# UserInteractive.net
KiCad netlist of a schematic drawn in Altium Designer
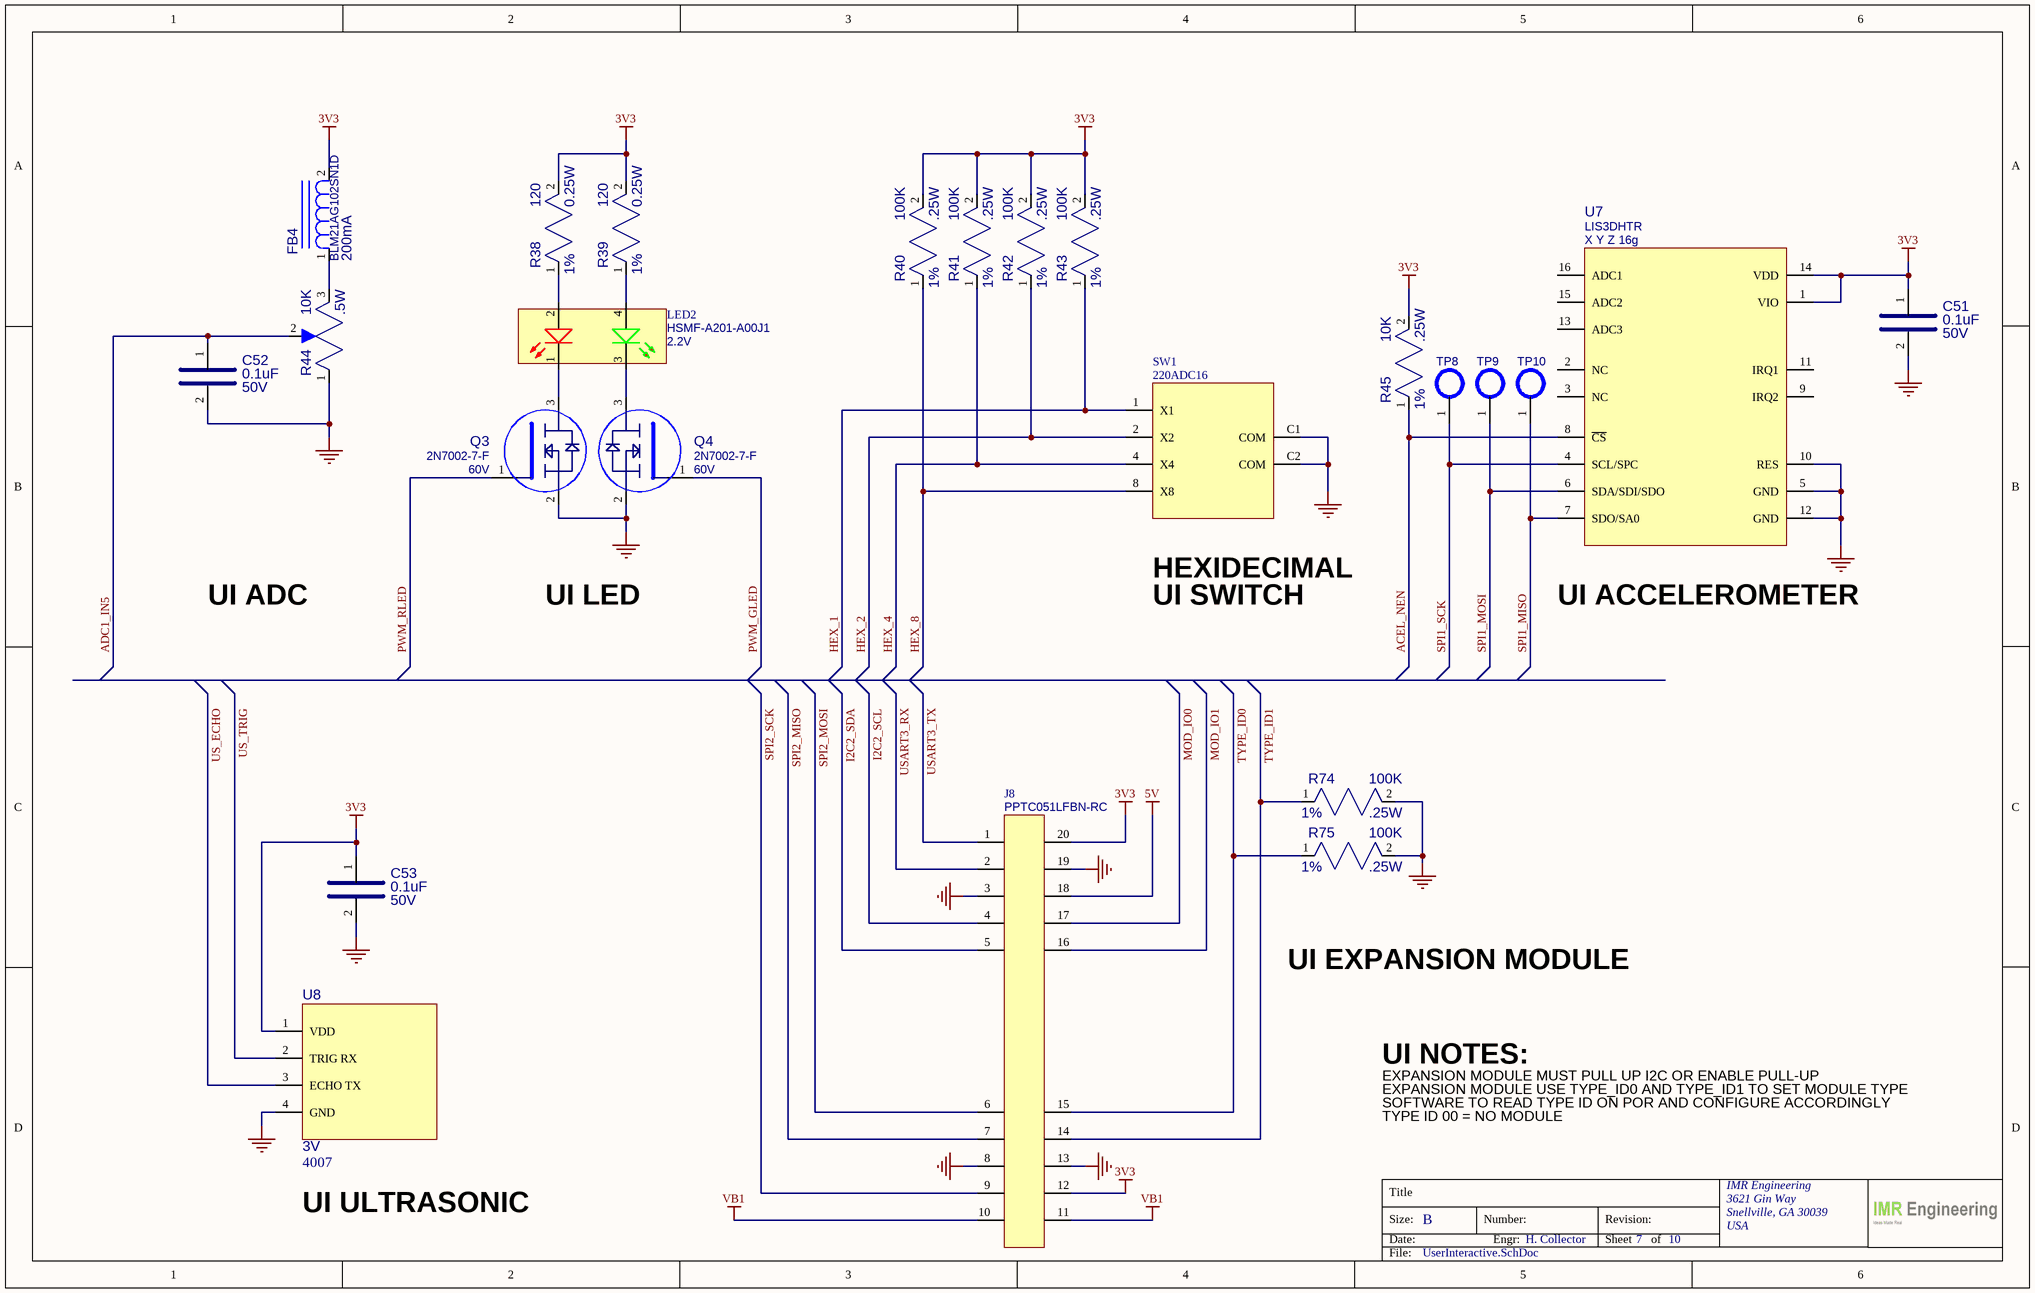
[diagram p0: UserInteractive.SchDoc]

(export (version "E")
  (design (tool "Eeschema 10.0.6"))
  (components
    (comp (ref "C51")
      (value "0.1uF")
      (footprint "CAP_0805")
      (description "CAP CER 0.1UF 50V X7R 0805")
      (fields (field (name "MFG") "AVX") (field (name "TOLERANCE") "10%") (field (name "VOLTAGE") "50V"))
      (libsource (lib "IMR_Lib") (part "CAP_0.1UF_50V_0805"))
    )
    (comp (ref "C52")
      (value "0.1uF")
      (footprint "CAP_0805")
      (description "CAP CER 0.1UF 50V X7R 0805")
      (fields (field (name "MFG") "AVX") (field (name "TOLERANCE") "10%") (field (name "VOLTAGE") "50V"))
      (libsource (lib "IMR_Lib") (part "CAP_0.1UF_50V_0805"))
    )
    (comp (ref "C53")
      (value "0.1uF")
      (footprint "CAP_0805")
      (description "CAP CER 0.1UF 50V X7R 0805")
      (fields (field (name "MFG") "AVX") (field (name "TOLERANCE") "10%") (field (name "VOLTAGE") "50V"))
      (libsource (lib "IMR_Lib") (part "CAP_0.1UF_50V_0805"))
    )
    (comp (ref "FB4")
      (value "200mA")
      (footprint "RES_0805")
      (description "FERRITE, 1KOHM AT 100MHZ, 220MA, .450DCR")
      (fields
        (field (name "MFG") "MURATA")
        (field (name "TOLERANCE") "10%")
        (field (name "MFG_PN") "BLM21AG102SN1D")
      )
      (libsource (lib "IMR_Lib") (part "FERRITE_BLM21AG102SN1D"))
    )
    (comp (ref "J8")
      (value "PPTC051LFBN-RC")
      (footprint "CONN_EXPANSION_BOARD")
      (description "CONN HEADER VERT 5POS 2.54MM (NOTE: QTY x4)")
      (fields (field (name "MFG") "Sullins Connector Solutions"))
      (libsource (lib "IMR_Lib") (part "CONN_TD_EXPANSION_MODULE"))
    )
    (comp (ref "LED2")
      (value "2.2V")
      (footprint "4PLCC-LED")
      (description "LED GREEN/RED CLEAR 4PLCC SMD")
      (fields
        (field (name "MFG") "Broadcom Limited")
        (field (name "MFG_PN") "HSMF-A201-A00J1")
        (field (name "Comment") "HSMF-A201-A00J1")
      )
      (libsource (lib "IMR_Lib") (part "LED_RED_GREEN_HSMF-A201-A00J1"))
    )
    (comp (ref "Q3")
      (value "60V")
      (footprint "SOT-23")
      (description "MOSFET N-CH 60V 115MA SOT23-3")
      (fields
        (field (name "MFG") "Diodes Incorporated")
        (field (name "MFG_PN") "2N7002-7-F")
        (field (name "Comment") "2N7002-7-F")
      )
      (libsource (lib "IMR_Lib") (part "MOSFET_NCH_2N7002-7-F"))
    )
    (comp (ref "Q4")
      (value "60V")
      (footprint "SOT-23")
      (description "MOSFET N-CH 60V 115MA SOT23-3")
      (fields
        (field (name "MFG") "Diodes Incorporated")
        (field (name "MFG_PN") "2N7002-7-F")
        (field (name "Comment") "2N7002-7-F")
      )
      (libsource (lib "") (part "MOSFET_NCH_2N7002-7-F_1"))
    )
    (comp (ref "R38")
      (value "120")
      (footprint "PMG_RES_0805")
      (description "RES 120 OHM 1% 1/4W 0805")
      (fields
        (field (name "MFG") "KOA Speer Electronics, Inc.")
        (field (name "TOLERANCE") "1%")
        (field (name "POWER") "0.25W")
        (field (name "Comment") "RK73H2ATTD1200F")
      )
      (libsource (lib "IMR_Lib") (part "RES_120_0805_1/4W_1%"))
    )
    (comp (ref "R39")
      (value "120")
      (footprint "PMG_RES_0805")
      (description "RES 120 OHM 1% 1/4W 0805")
      (fields
        (field (name "MFG") "KOA Speer Electronics, Inc.")
        (field (name "TOLERANCE") "1%")
        (field (name "POWER") "0.25W")
        (field (name "Comment") "RK73H2ATTD1200F")
      )
      (libsource (lib "IMR_Lib") (part "RES_120_0805_1/4W_1%"))
    )
    (comp (ref "R40")
      (value "100K")
      (footprint "PMG_RES_0805")
      (description "RES SMD 100K OHM 1% 1/4W 0805")
      (fields
        (field (name "MFG") "KOA Speer Electronics, Inc.")
        (field (name "TOLERANCE") "1%")
        (field (name "POWER") ".25W")
        (field (name "Comment") "RK73H2ATTD1003F")
      )
      (libsource (lib "IMR_Lib") (part "RES_100K_0805_1/4W_1%"))
    )
    (comp (ref "R41")
      (value "100K")
      (footprint "PMG_RES_0805")
      (description "RES SMD 100K OHM 1% 1/4W 0805")
      (fields
        (field (name "MFG") "KOA Speer Electronics, Inc.")
        (field (name "TOLERANCE") "1%")
        (field (name "POWER") ".25W")
        (field (name "Comment") "RK73H2ATTD1003F")
      )
      (libsource (lib "IMR_Lib") (part "RES_100K_0805_1/4W_1%"))
    )
    (comp (ref "R42")
      (value "100K")
      (footprint "PMG_RES_0805")
      (description "RES SMD 100K OHM 1% 1/4W 0805")
      (fields
        (field (name "MFG") "KOA Speer Electronics, Inc.")
        (field (name "TOLERANCE") "1%")
        (field (name "POWER") ".25W")
        (field (name "Comment") "RK73H2ATTD1003F")
      )
      (libsource (lib "IMR_Lib") (part "RES_100K_0805_1/4W_1%"))
    )
    (comp (ref "R43")
      (value "100K")
      (footprint "PMG_RES_0805")
      (description "RES SMD 100K OHM 1% 1/4W 0805")
      (fields
        (field (name "MFG") "KOA Speer Electronics, Inc.")
        (field (name "TOLERANCE") "1%")
        (field (name "POWER") ".25W")
        (field (name "Comment") "RK73H2ATTD1003F")
      )
      (libsource (lib "IMR_Lib") (part "RES_100K_0805_1/4W_1%"))
    )
    (comp (ref "R44")
      (value "10K")
      (footprint "BOURNS_3386F")
      (description "TRIMMER 10K OHM 0.5W PC PIN TOP")
      (fields
        (field (name "MFG") "Bourns Inc.")
        (field (name "POWER") ".5W")
        (field (name "Comment") "3386F-1-103TLF")
      )
      (libsource (lib "IMR_Lib") (part "RES_POT_10K_500mW"))
    )
    (comp (ref "R45")
      (value "10K")
      (footprint "RES_0805")
      (description "RES SMD 10K OHM 1% 1/4W 0805")
      (fields
        (field (name "MFG") "KOA Speer Electronics, Inc.")
        (field (name "TOLERANCE") "1%")
        (field (name "POWER") ".25W")
        (field (name "Comment") "SG73S2ATTD1002F")
      )
      (libsource (lib "IMR_Lib") (part "RES_10K_0805_1/4W_1%"))
    )
    (comp (ref "R74")
      (value "100K")
      (footprint "PMG_RES_0805")
      (description "RES SMD 100K OHM 1% 1/4W 0805")
      (fields
        (field (name "MFG") "KOA Speer Electronics, Inc.")
        (field (name "TOLERANCE") "1%")
        (field (name "POWER") ".25W")
        (field (name "Comment") "RK73H2ATTD1003F")
      )
      (libsource (lib "IMR_Lib") (part "RES_100K_0805_1/4W_1%"))
    )
    (comp (ref "R75")
      (value "100K")
      (footprint "PMG_RES_0805")
      (description "RES SMD 100K OHM 1% 1/4W 0805")
      (fields
        (field (name "MFG") "KOA Speer Electronics, Inc.")
        (field (name "TOLERANCE") "1%")
        (field (name "POWER") ".25W")
        (field (name "Comment") "RK73H2ATTD1003F")
      )
      (libsource (lib "IMR_Lib") (part "RES_100K_0805_1/4W_1%"))
    )
    (comp (ref "SW1")
      (value "220ADC16")
      (footprint "CTS_220ADC16")
      (description "SWITCH ROTARY DIP HEX 100MA 50V")
      (fields (field (name "MFG") "CTS Electrocomponents"))
      (libsource (lib "IMR_Lib") (part "SW_DIP_220ADC16"))
    )
    (comp (ref "TP8")
      (value "TP_0635MM_HOLE")
      (footprint "TP_0635MM_HOLE")
      (description "3MM IN D. MT HOLE")
      (libsource (lib "IMR_Lib") (part "TP_0635MM_HOLE"))
    )
    (comp (ref "TP9")
      (value "TP_0635MM_HOLE")
      (footprint "TP_0635MM_HOLE")
      (description "3MM IN D. MT HOLE")
      (libsource (lib "IMR_Lib") (part "TP_0635MM_HOLE"))
    )
    (comp (ref "TP10")
      (value "TP_0635MM_HOLE")
      (footprint "TP_0635MM_HOLE")
      (description "3MM IN D. MT HOLE")
      (libsource (lib "IMR_Lib") (part "TP_0635MM_HOLE"))
    )
    (comp (ref "U7")
      (value "X Y Z 16g")
      (footprint "XDCR_LIS3DHTR")
      (description "ACCEL 2-16G I2C/SPI 16LGA")
      (fields
        (field (name "MFG") "STMicroelectronics")
        (field (name "MFG_PN") "LIS3DHTR")
        (field (name "Comment") "LIS3DHTR")
      )
      (libsource (lib "IMR_Lib") (part "IC_LIS3DHTR"))
    )
    (comp (ref "U8")
      (value "3V")
      (footprint "4007")
      (description "MODULE ULTRASONIC SENSOR 3V")
      (fields
        (field (name "MFG") "Adafruit Industries LLC")
        (field (name "MFG_PN") "4007")
        (field (name "Comment") "4007")
      )
      (libsource (lib "IMR_Lib") (part "MODULE_RCWL-1601"))
    )
  )
  (nets
    (net (code "1") (name "/ACEL_NEN") (class "Default")
      (node (ref "R45") (pin "1") (pinfunction "1_1") (pintype "passive"))
      (node (ref "U7") (pin "8") (pinfunction "CS_8") (pintype "passive"))
    )
    (net (code "2") (name "/ADC1_IN5") (class "Default")
      (node (ref "C52") (pin "1") (pinfunction "1_1") (pintype "passive"))
      (node (ref "R44") (pin "2") (pinfunction "2_2") (pintype "passive"))
    )
    (net (code "3") (name "/HEX_1") (class "Default")
      (node (ref "R43") (pin "1") (pinfunction "1_1") (pintype "passive"))
      (node (ref "SW1") (pin "1") (pinfunction "X1_1") (pintype "passive"))
    )
    (net (code "4") (name "/HEX_2") (class "Default")
      (node (ref "R42") (pin "1") (pinfunction "1_1") (pintype "passive"))
      (node (ref "SW1") (pin "2") (pinfunction "X2_2") (pintype "passive"))
    )
    (net (code "5") (name "/HEX_4") (class "Default")
      (node (ref "R41") (pin "1") (pinfunction "1_1") (pintype "passive"))
      (node (ref "SW1") (pin "4") (pinfunction "X4_4") (pintype "passive"))
    )
    (net (code "6") (name "/HEX_8") (class "Default")
      (node (ref "R40") (pin "1") (pinfunction "1_1") (pintype "passive"))
      (node (ref "SW1") (pin "8") (pinfunction "X8_8") (pintype "passive"))
    )
    (net (code "7") (name "/I2C2_SCL") (class "Default") (node (ref "J8") (pin "4") (pintype "passive")))
    (net (code "8") (name "/I2C2_SDA") (class "Default") (node (ref "J8") (pin "5") (pintype "passive")))
    (net (code "9") (name "/MOD_IO0") (class "Default")
      (node (ref "J8") (pin "17") (pinfunction "17_17") (pintype "passive"))
    )
    (net (code "10") (name "/MOD_IO1") (class "Default")
      (node (ref "J8") (pin "16") (pinfunction "16_16") (pintype "passive"))
    )
    (net (code "11") (name "/PWM_GLED") (class "Default")
      (node (ref "Q4") (pin "1") (pinfunction "B_1") (pintype "passive"))
    )
    (net (code "12") (name "/PWM_RLED") (class "Default")
      (node (ref "Q3") (pin "1") (pinfunction "B_1") (pintype "passive"))
    )
    (net (code "13") (name "/SPI1_MISO") (class "Default")
      (node (ref "TP10") (pin "1") (pinfunction "1_1") (pintype "passive"))
      (node (ref "U7") (pin "7") (pinfunction "SDO/SA0_7") (pintype "passive"))
    )
    (net (code "14") (name "/SPI1_MOSI") (class "Default")
      (node (ref "TP9") (pin "1") (pinfunction "1_1") (pintype "passive"))
      (node (ref "U7") (pin "6") (pinfunction "SDA/SDI/SDO_6") (pintype "passive"))
    )
    (net (code "15") (name "/SPI1_SCK") (class "Default")
      (node (ref "TP8") (pin "1") (pinfunction "1_1") (pintype "passive"))
      (node (ref "U7") (pin "4") (pinfunction "SCL/SPC_4") (pintype "passive"))
    )
    (net (code "16") (name "/SPI2_MISO") (class "Default")
      (node (ref "J8") (pin "7") (pinfunction "7_7") (pintype "passive"))
    )
    (net (code "17") (name "/SPI2_MOSI") (class "Default") (node (ref "J8") (pin "6") (pintype "passive")))
    (net (code "18") (name "/SPI2_SCK") (class "Default")
      (node (ref "J8") (pin "9") (pinfunction "9_9") (pintype "passive"))
    )
    (net (code "19") (name "/TYPE_ID0") (class "Default")
      (node (ref "J8") (pin "15") (pinfunction "15_15") (pintype "passive"))
      (node (ref "R75") (pin "1") (pinfunction "1_1") (pintype "passive"))
    )
    (net (code "20") (name "/TYPE_ID1") (class "Default")
      (node (ref "J8") (pin "14") (pinfunction "14_14") (pintype "passive"))
      (node (ref "R74") (pin "1") (pinfunction "1_1") (pintype "passive"))
    )
    (net (code "21") (name "/USART3_RX") (class "Default") (node (ref "J8") (pin "2") (pintype "passive")))
    (net (code "22") (name "/USART3_TX") (class "Default")
      (node (ref "J8") (pin "1") (pinfunction "1_1") (pintype "passive"))
    )
    (net (code "23") (name "/US_ECHO") (class "Default")
      (node (ref "U8") (pin "3") (pinfunction "ECHO_TX_3") (pintype "passive"))
    )
    (net (code "24") (name "/US_TRIG") (class "Default")
      (node (ref "U8") (pin "2") (pinfunction "TRIG_RX_2") (pintype "passive"))
    )
    (net (code "25") (name "3V3") (class "Default")
      (node (ref "C51") (pin "1") (pinfunction "1_1") (pintype "passive"))
      (node (ref "C53") (pin "1") (pinfunction "1_1") (pintype "passive"))
      (node (ref "FB4") (pin "2") (pinfunction "2_2") (pintype "passive"))
      (node (ref "J8") (pin "12") (pinfunction "12_12") (pintype "passive"))
      (node (ref "J8") (pin "20") (pinfunction "20_20") (pintype "passive"))
      (node (ref "R38") (pin "2") (pinfunction "2_2") (pintype "passive"))
      (node (ref "R39") (pin "2") (pinfunction "2_2") (pintype "passive"))
      (node (ref "R40") (pin "2") (pinfunction "2_2") (pintype "passive"))
      (node (ref "R41") (pin "2") (pinfunction "2_2") (pintype "passive"))
      (node (ref "R42") (pin "2") (pinfunction "2_2") (pintype "passive"))
      (node (ref "R43") (pin "2") (pinfunction "2_2") (pintype "passive"))
      (node (ref "R45") (pin "2") (pinfunction "2_2") (pintype "passive"))
      (node (ref "U7") (pin "1") (pinfunction "VIO_1") (pintype "passive"))
      (node (ref "U7") (pin "14") (pinfunction "VDD_14") (pintype "passive"))
      (node (ref "U8") (pin "1") (pinfunction "VDD_1") (pintype "passive"))
    )
    (net (code "26") (name "5V") (class "Default")
      (node (ref "J8") (pin "18") (pinfunction "18_18") (pintype "passive"))
    )
    (net (code "27") (name "GND") (class "Default")
      (node (ref "C51") (pin "2") (pinfunction "2_2") (pintype "passive"))
      (node (ref "C52") (pin "2") (pinfunction "2_2") (pintype "passive"))
      (node (ref "C53") (pin "2") (pinfunction "2_2") (pintype "passive"))
      (node (ref "J8") (pin "13") (pinfunction "13_13") (pintype "passive"))
      (node (ref "J8") (pin "19") (pinfunction "19_19") (pintype "passive"))
      (node (ref "J8") (pin "3") (pintype "passive"))
      (node (ref "J8") (pin "8") (pinfunction "8_8") (pintype "passive"))
      (node (ref "Q3") (pin "2") (pinfunction "E_2") (pintype "passive"))
      (node (ref "Q4") (pin "2") (pinfunction "E_2") (pintype "passive"))
      (node (ref "R44") (pin "1") (pinfunction "1_1") (pintype "passive"))
      (node (ref "R74") (pin "2") (pinfunction "2_2") (pintype "passive"))
      (node (ref "R75") (pin "2") (pinfunction "2_2") (pintype "passive"))
      (node (ref "SW1") (pin "C1") (pinfunction "COM_C1") (pintype "passive"))
      (node (ref "SW1") (pin "C2") (pinfunction "COM_C2") (pintype "passive"))
      (node (ref "U7") (pin "10") (pinfunction "RES_10") (pintype "passive"))
      (node (ref "U7") (pin "12") (pinfunction "GND_12") (pintype "passive"))
      (node (ref "U7") (pin "5") (pinfunction "GND_5") (pintype "passive"))
      (node (ref "U8") (pin "4") (pinfunction "GND_4") (pintype "passive"))
    )
    (net (code "28") (name "Net-(FB4-Pad1)") (class "Default")
      (node (ref "FB4") (pin "1") (pinfunction "1_1") (pintype "passive"))
      (node (ref "R44") (pin "3") (pinfunction "3_3") (pintype "passive"))
    )
    (net (code "29") (name "Net-(LED2-A-Pad2)") (class "Default")
      (node (ref "LED2") (pin "2") (pinfunction "A_2") (pintype "passive"))
      (node (ref "R38") (pin "1") (pinfunction "1_1") (pintype "passive"))
    )
    (net (code "30") (name "Net-(LED2-A-Pad4)") (class "Default")
      (node (ref "LED2") (pin "4") (pinfunction "A_4") (pintype "passive"))
      (node (ref "R39") (pin "1") (pinfunction "1_1") (pintype "passive"))
    )
    (net (code "31") (name "Net-(Q3-C)") (class "Default")
      (node (ref "LED2") (pin "1") (pinfunction "K_1") (pintype "passive"))
      (node (ref "Q3") (pin "3") (pinfunction "C_3") (pintype "passive"))
    )
    (net (code "32") (name "Net-(Q4-C)") (class "Default")
      (node (ref "LED2") (pin "3") (pinfunction "K_3") (pintype "passive"))
      (node (ref "Q4") (pin "3") (pinfunction "C_3") (pintype "passive"))
    )
    (net (code "33") (name "VB1") (class "Default")
      (node (ref "J8") (pin "10") (pinfunction "10_10") (pintype "passive"))
      (node (ref "J8") (pin "11") (pinfunction "11_11") (pintype "passive"))
    )
    (net (code "34") (name "unconnected-(U7-ADC1-Pad16)") (class "Default")
      (node (ref "U7") (pin "16") (pinfunction "ADC1_16") (pintype "passive"))
    )
    (net (code "35") (name "unconnected-(U7-ADC2-Pad15)") (class "Default")
      (node (ref "U7") (pin "15") (pinfunction "ADC2_15") (pintype "passive"))
    )
    (net (code "36") (name "unconnected-(U7-ADC3-Pad13)") (class "Default")
      (node (ref "U7") (pin "13") (pinfunction "ADC3_13") (pintype "passive"))
    )
    (net (code "37") (name "unconnected-(U7-IRQ1-Pad11)") (class "Default")
      (node (ref "U7") (pin "11") (pinfunction "IRQ1_11") (pintype "passive"))
    )
    (net (code "38") (name "unconnected-(U7-IRQ2-Pad9)") (class "Default")
      (node (ref "U7") (pin "9") (pinfunction "IRQ2_9") (pintype "passive"))
    )
    (net (code "39") (name "unconnected-(U7-NC-Pad2)") (class "Default")
      (node (ref "U7") (pin "2") (pinfunction "NC_2") (pintype "passive"))
    )
    (net (code "40") (name "unconnected-(U7-NC-Pad3)") (class "Default")
      (node (ref "U7") (pin "3") (pinfunction "NC_3") (pintype "passive"))
    )
  )
)
